# ee453_pcb_N-B-S.net
KiCad netlist of a schematic drawn in Altium Designer
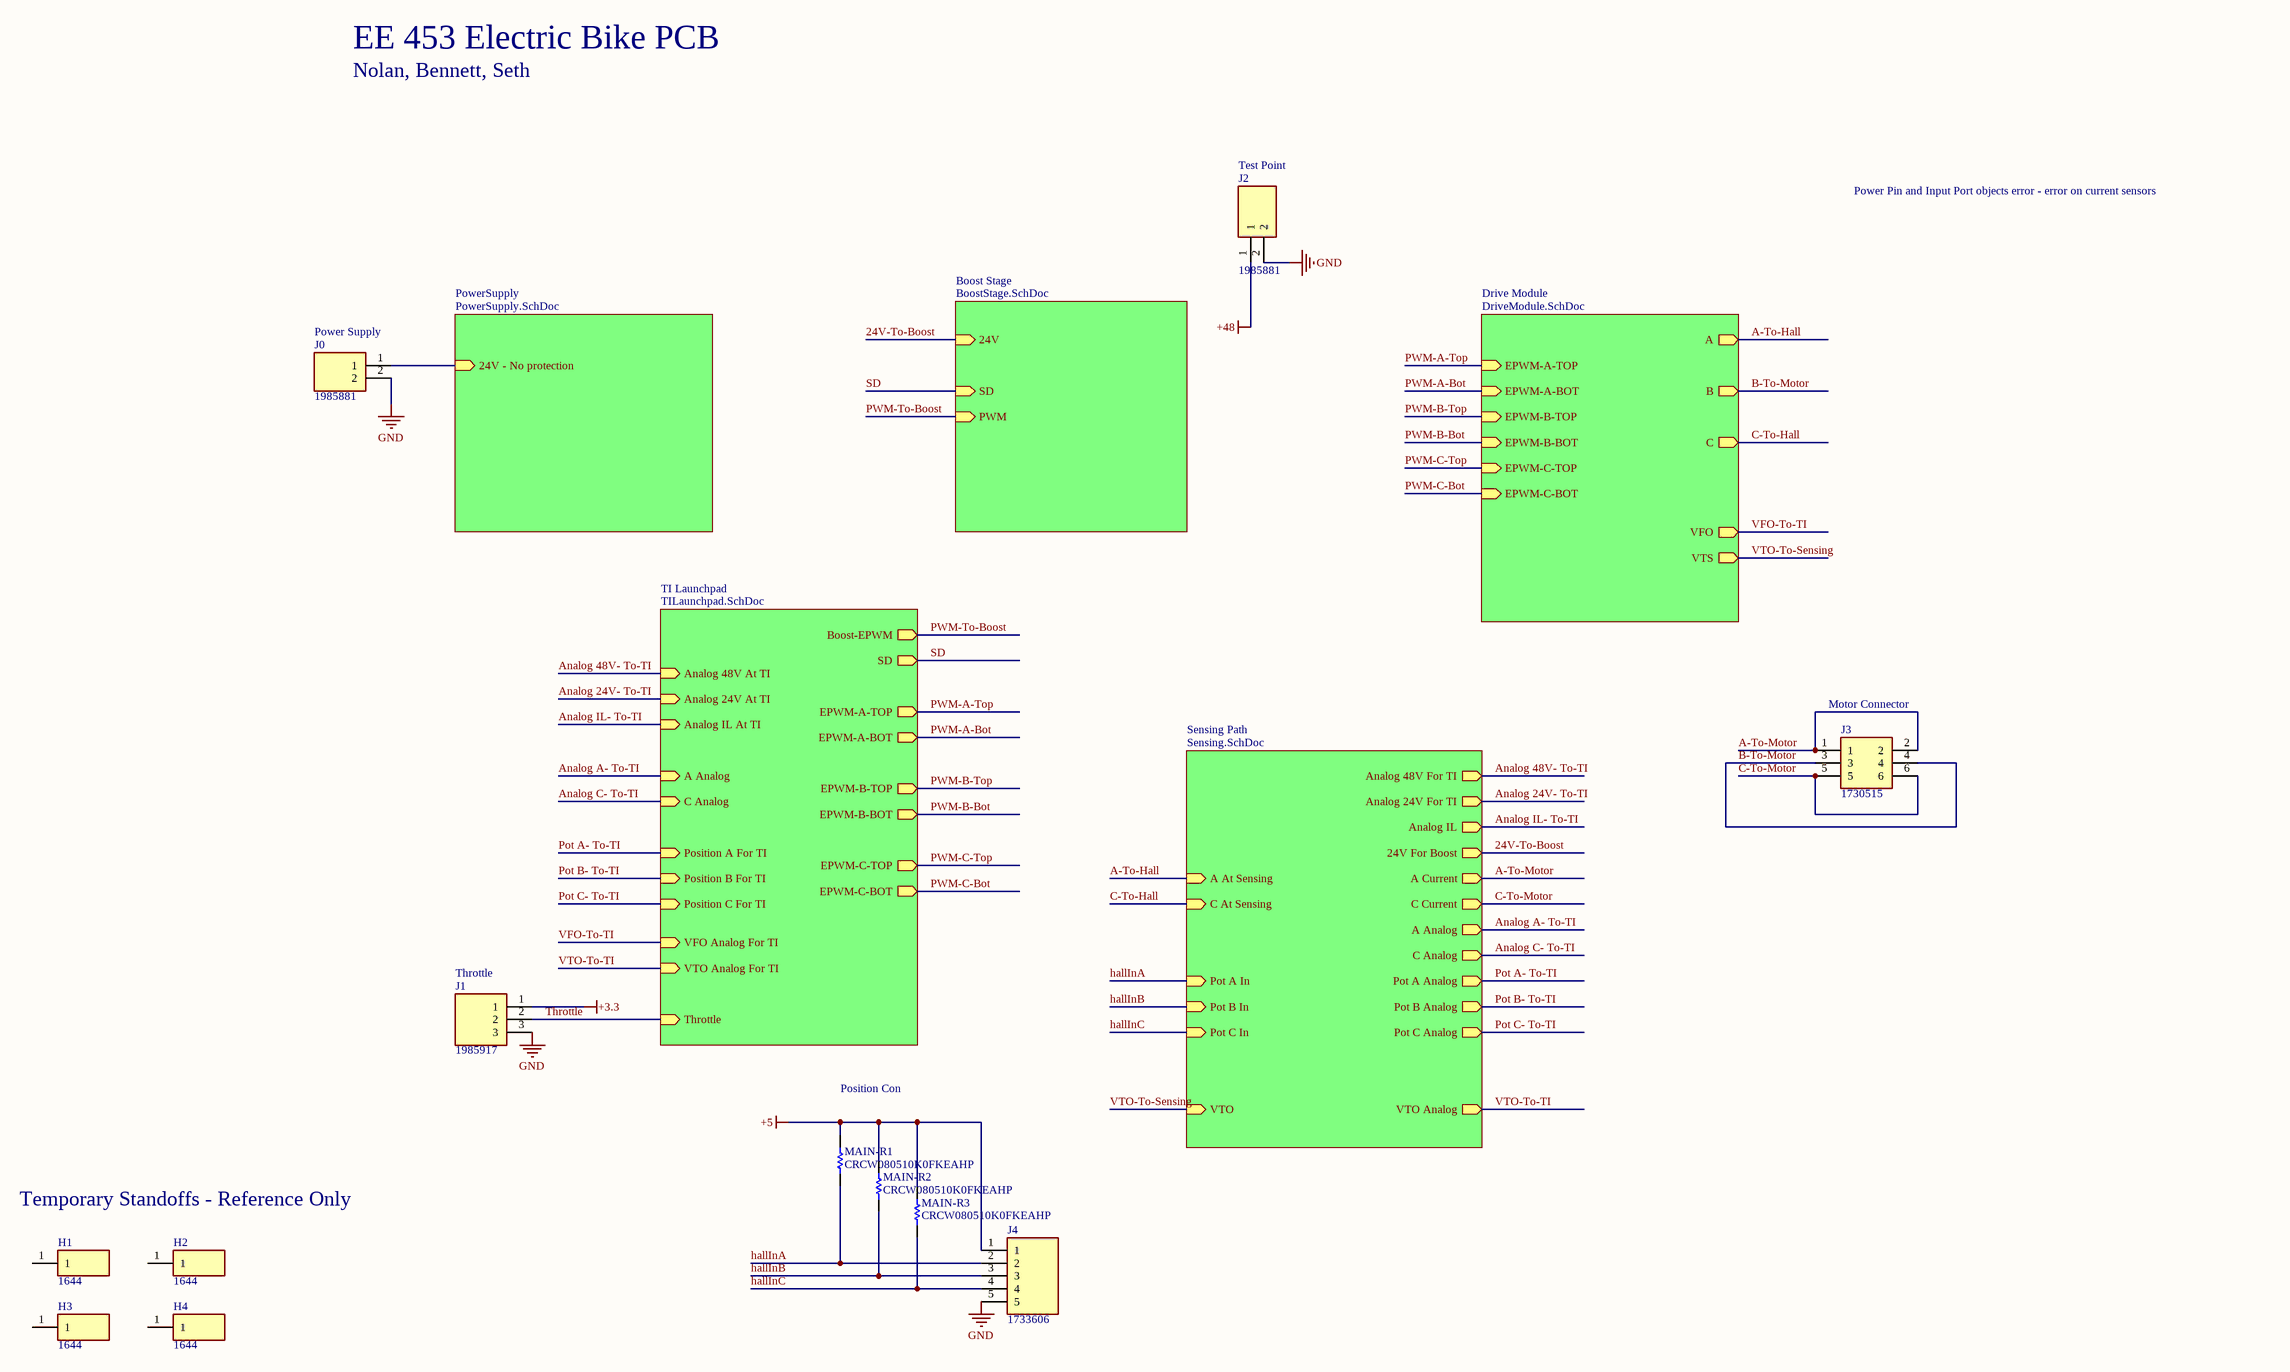
[diagram p0: ee453_pcb_N-B-S.SchDoc]

(export (version "E")
  (design (tool "Eeschema 10.0.6"))
  (components
    (comp (ref "H1")
      (value "1644")
      (footprint "SamacSys:1644")
      (description "Hardware")
      (fields (field (name "MOUSER PART NUMBER") "534-1644"))
      (libsource (lib "SamacSys") (part "1644"))
    )
    (comp (ref "H2")
      (value "1644")
      (footprint "SamacSys:1644")
      (description "Hardware")
      (fields (field (name "MOUSER PART NUMBER") "534-1644"))
      (libsource (lib "SamacSys") (part "1644"))
    )
    (comp (ref "H3")
      (value "1644")
      (footprint "SamacSys:1644")
      (description "Hardware")
      (fields (field (name "MOUSER PART NUMBER") "534-1644"))
      (libsource (lib "SamacSys") (part "1644"))
    )
    (comp (ref "H4")
      (value "1644")
      (footprint "SamacSys:1644")
      (description "Hardware")
      (fields (field (name "MOUSER PART NUMBER") "534-1644"))
      (libsource (lib "SamacSys") (part "1644"))
    )
    (comp (ref "J0")
      (value "1985881")
      (footprint "SamacSys:1985881")
      (description "Connector")
      (libsource (lib "*") (part "1985881"))
    )
    (comp (ref "J1")
      (value "1985917")
      (footprint "SamacSys:1985917")
      (description "Connector")
      (fields (field (name "MOUSER PART NUMBER") "651-1985917"))
      (libsource (lib "*") (part "1985917"))
    )
    (comp (ref "J2")
      (value "1985881")
      (footprint "SamacSys:1985881")
      (description "Connector")
      (libsource (lib "") (part "1985881_1"))
    )
    (comp (ref "J3")
      (value "1730515")
      (footprint "SamacSys:1730515")
      (description "Connector")
      (fields (field (name "MOUSER PART NUMBER") "651-1730515"))
      (libsource (lib "*") (part "1730515"))
    )
    (comp (ref "J4")
      (value "1733606")
      (footprint "SamacSys:1733606")
      (description "Connector")
      (fields (field (name "MOUSER PART NUMBER") "651-1733606"))
      (libsource (lib "*") (part "1733606"))
    )
    (comp (ref "MAIN-R1")
      (value "CRCW080510K0FKEAHP")
      (footprint "RESC2013X60X40NL15T20")
      (fields (field (name "MANUFACTURER") "Vishay Dale"))
      (libsource (lib "Altium Content Vault") (part "RES"))
    )
    (comp (ref "MAIN-R2")
      (value "CRCW080510K0FKEAHP")
      (footprint "RESC2013X60X40NL15T20")
      (fields (field (name "MANUFACTURER") "Vishay Dale"))
      (libsource (lib "Altium Content Vault") (part "RES"))
    )
    (comp (ref "MAIN-R3")
      (value "CRCW080510K0FKEAHP")
      (footprint "RESC2013X60X40NL15T20")
      (fields (field (name "MANUFACTURER") "Vishay Dale"))
      (libsource (lib "Altium Content Vault") (part "RES"))
    )
  )
  (nets
    (net (code "1") (name "+3.3") (class "Default")
      (node (ref "J1") (pin "1") (pinfunction "1_1") (pintype "passive"))
    )
    (net (code "2") (name "+5") (class "Default")
      (node (ref "J4") (pin "1") (pinfunction "1_1") (pintype "passive"))
      (node (ref "MAIN-R1") (pin "2") (pinfunction "2_2") (pintype "passive"))
      (node (ref "MAIN-R2") (pin "2") (pinfunction "2_2") (pintype "passive"))
      (node (ref "MAIN-R3") (pin "2") (pinfunction "2_2") (pintype "passive"))
    )
    (net (code "3") (name "+48") (class "Default")
      (node (ref "J2") (pin "1") (pinfunction "1_1") (pintype "passive"))
    )
    (net (code "4") (name "/24V - No protection") (class "Default")
      (node (ref "J0") (pin "1") (pinfunction "1_1") (pintype "passive"))
    )
    (net (code "7") (name "/A-To-Motor") (class "Default")
      (node (ref "J3") (pin "1") (pinfunction "1_1") (pintype "passive"))
      (node (ref "J3") (pin "2") (pinfunction "2_2") (pintype "passive"))
    )
    (net (code "13") (name "/B-To-Motor") (class "Default")
      (node (ref "J3") (pin "3") (pinfunction "3_3") (pintype "passive"))
      (node (ref "J3") (pin "4") (pinfunction "4_4") (pintype "passive"))
    )
    (net (code "15") (name "/C-To-Motor") (class "Default")
      (node (ref "J3") (pin "5") (pinfunction "5_5") (pintype "passive"))
      (node (ref "J3") (pin "6") (pinfunction "6_6") (pintype "passive"))
    )
    (net (code "27") (name "/Throttle") (class "Default")
      (node (ref "J1") (pin "2") (pinfunction "2_2") (pintype "passive"))
    )
    (net (code "31") (name "/hallInA") (class "Default")
      (node (ref "J4") (pin "2") (pinfunction "2_2") (pintype "passive"))
      (node (ref "MAIN-R1") (pin "1") (pinfunction "1_1") (pintype "passive"))
    )
    (net (code "32") (name "/hallInB") (class "Default")
      (node (ref "J4") (pin "3") (pinfunction "3_3") (pintype "passive"))
      (node (ref "MAIN-R2") (pin "1") (pinfunction "1_1") (pintype "passive"))
    )
    (net (code "33") (name "/hallInC") (class "Default")
      (node (ref "J4") (pin "4") (pinfunction "4_4") (pintype "passive"))
      (node (ref "MAIN-R3") (pin "1") (pinfunction "1_1") (pintype "passive"))
    )
    (net (code "34") (name "GND") (class "Default")
      (node (ref "J0") (pin "2") (pinfunction "2_2") (pintype "passive"))
      (node (ref "J1") (pin "3") (pinfunction "3_3") (pintype "passive"))
      (node (ref "J2") (pin "2") (pinfunction "2_2") (pintype "passive"))
      (node (ref "J4") (pin "5") (pinfunction "5_5") (pintype "passive"))
    )
    (net (code "35") (name "unconnected-(H1-Pad1)") (class "Default")
      (node (ref "H1") (pin "1") (pinfunction "1_1") (pintype "passive"))
    )
    (net (code "36") (name "unconnected-(H2-Pad1)") (class "Default")
      (node (ref "H2") (pin "1") (pinfunction "1_1") (pintype "passive"))
    )
    (net (code "37") (name "unconnected-(H3-Pad1)") (class "Default")
      (node (ref "H3") (pin "1") (pinfunction "1_1") (pintype "passive"))
    )
    (net (code "38") (name "unconnected-(H4-Pad1)") (class "Default")
      (node (ref "H4") (pin "1") (pinfunction "1_1") (pintype "passive"))
    )
  )
)
